# V2_eagle7.net
KiCad netlist of a schematic drawn in EAGLE
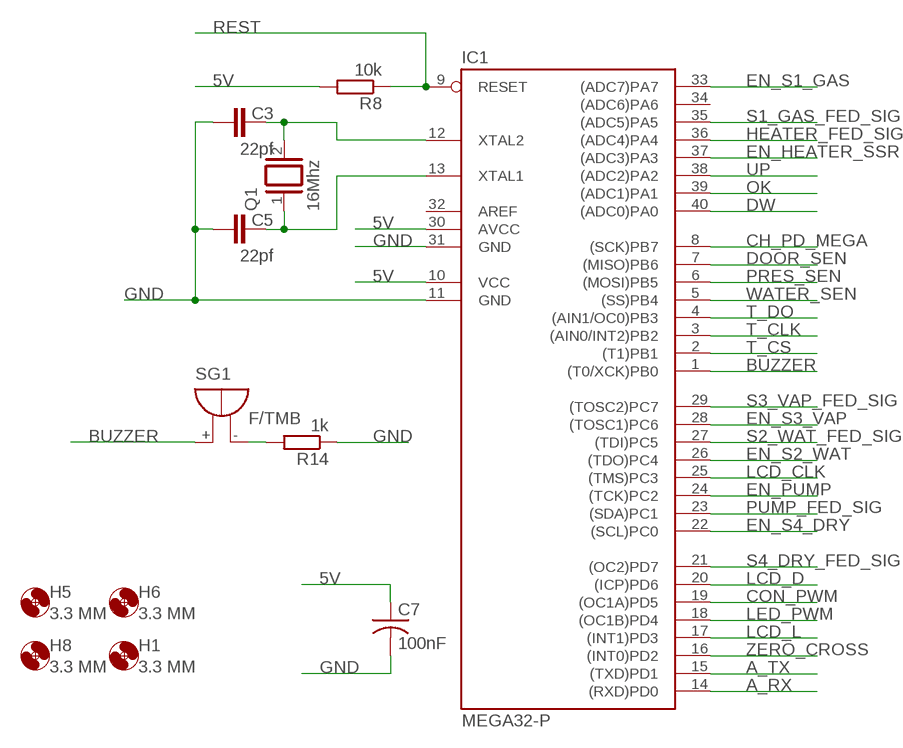
[diagram p0: schematic, sheet 1]
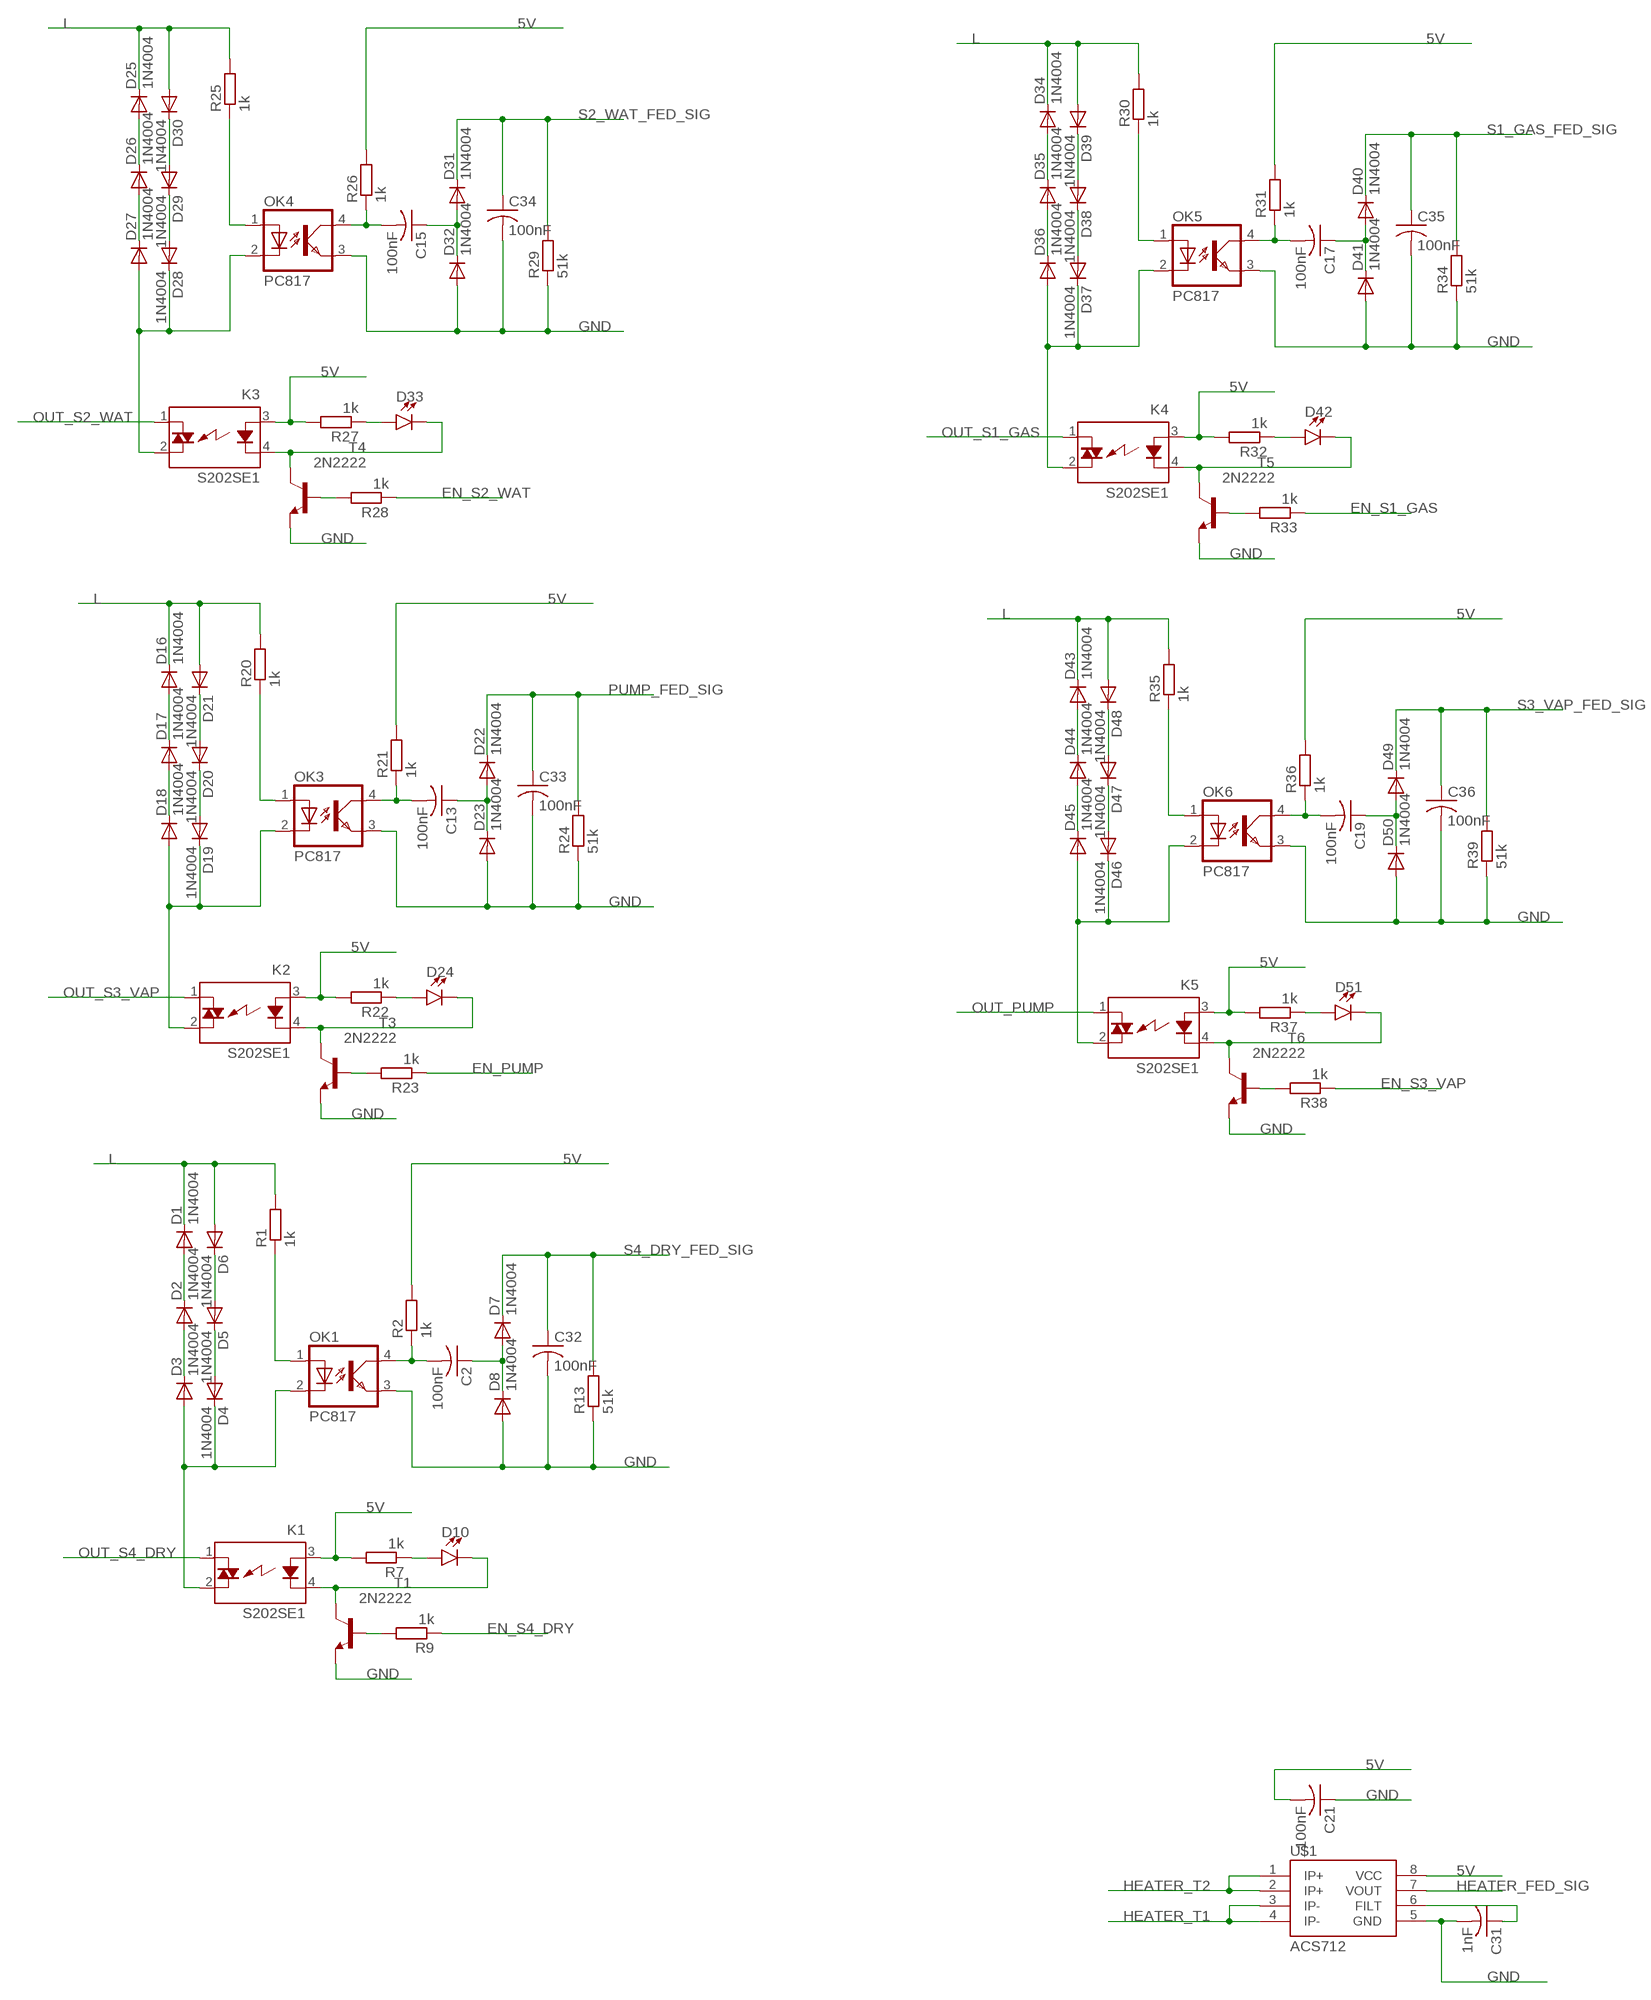
[diagram p1: schematic, sheet 2]
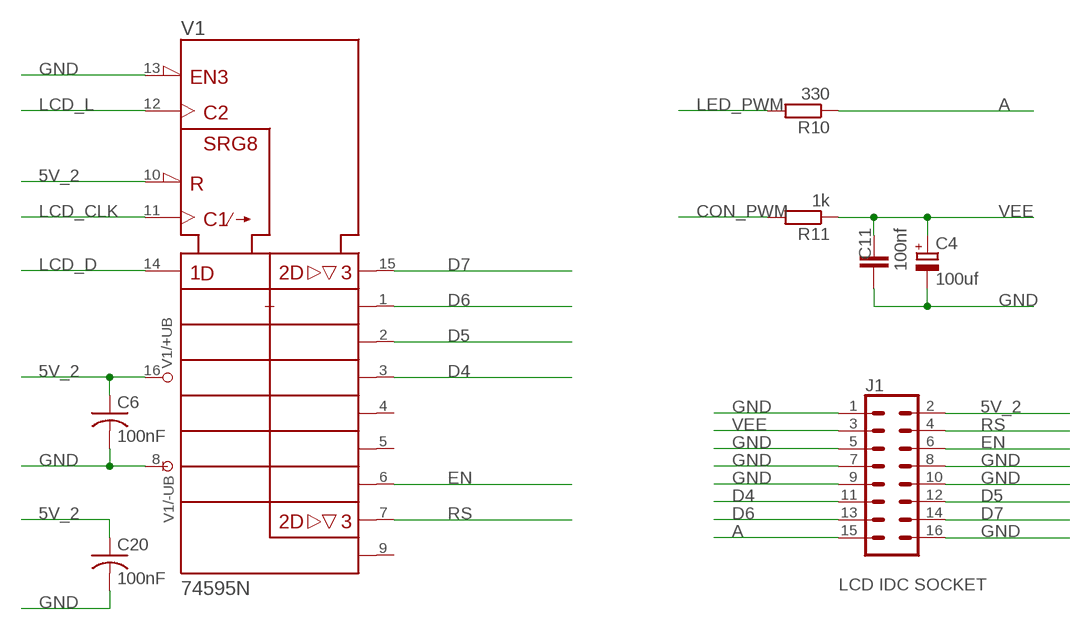
[diagram p2: schematic, sheet 3]
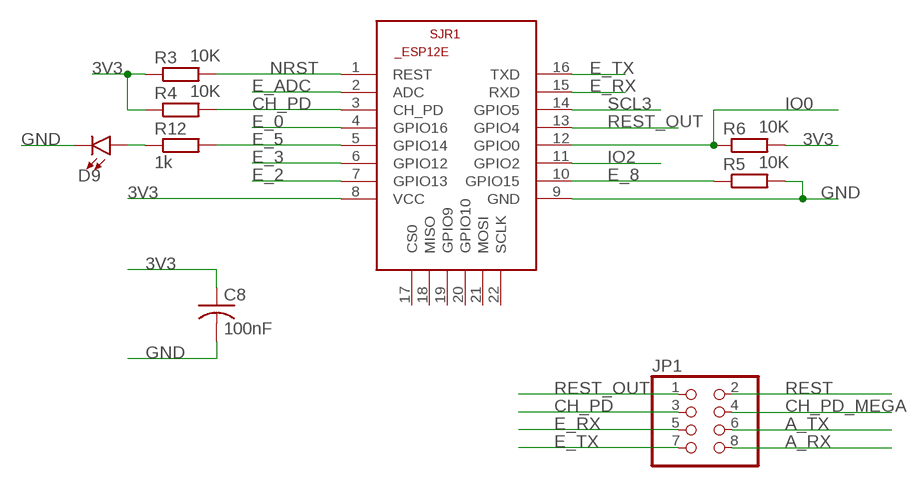
[diagram p3: schematic, sheet 4]
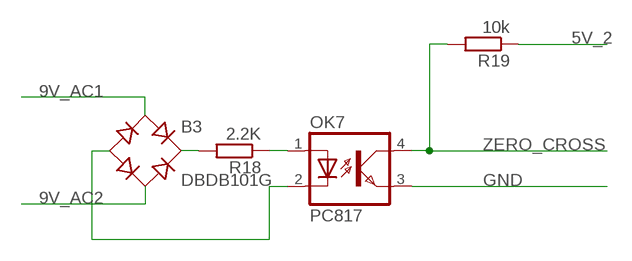
[diagram p4: schematic, sheet 5]
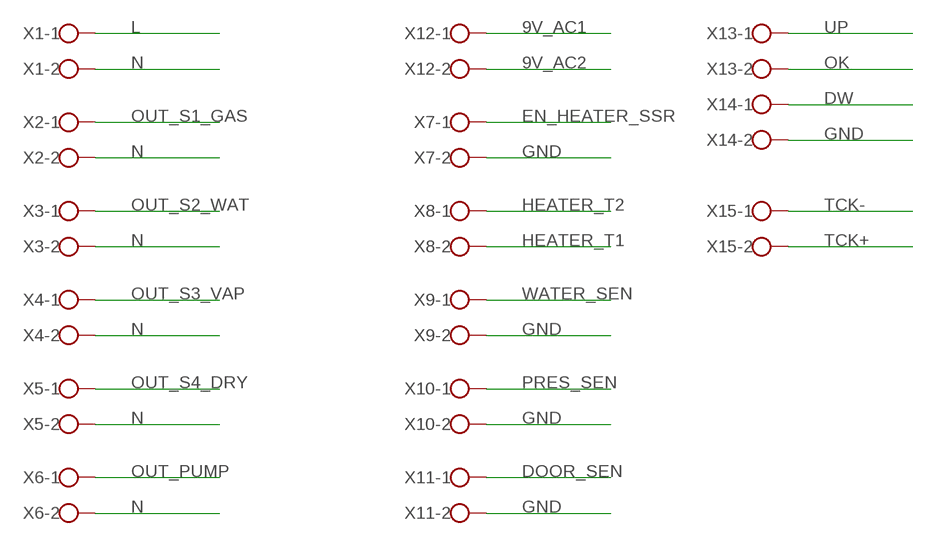
[diagram p5: schematic, sheet 6]
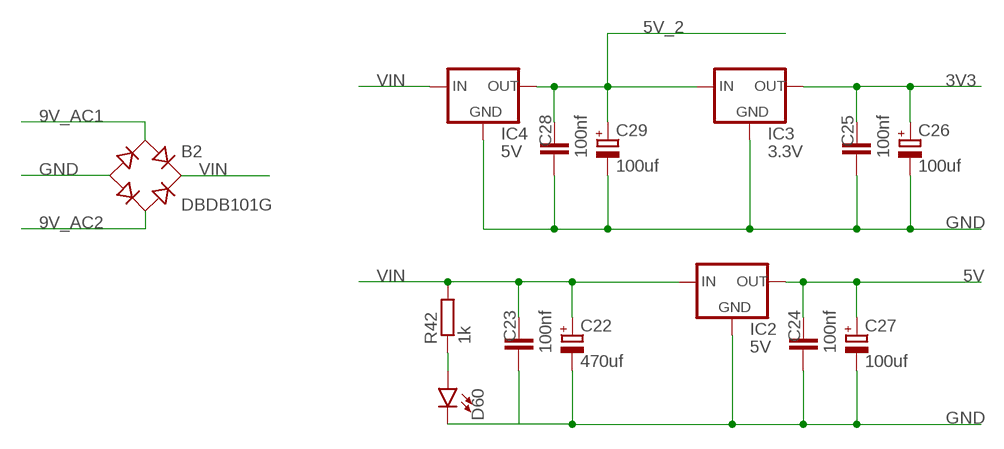
[diagram p6: schematic, sheet 7]
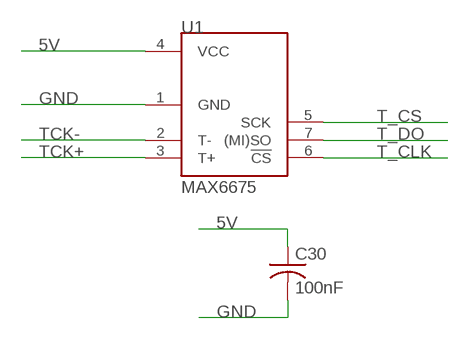
[diagram p7: schematic, sheet 8]

(export (version "E")
  (design (tool "Eeschema 10.0.6"))
  (components
    (comp (ref "C30")
      (value "100nF")
      (footprint "eagle-import:C050-035X075")
      (libsource (lib "eagle-import") (part "C-US050-035X075"))
    )
    (comp (ref "U1")
      (value "MAX6675")
      (footprint "eagle-import:SOIC8")
      (libsource (lib "eagle-import") (part "MAX6675"))
    )
    (comp (ref "C2")
      (value "100nF")
      (footprint "eagle-import:C050-035X075")
      (libsource (lib "eagle-import") (part "C-US050-035X075"))
    )
    (comp (ref "C13")
      (value "100nF")
      (footprint "eagle-import:C050-035X075")
      (libsource (lib "eagle-import") (part "C-US050-035X075"))
    )
    (comp (ref "C15")
      (value "100nF")
      (footprint "eagle-import:C050-035X075")
      (libsource (lib "eagle-import") (part "C-US050-035X075"))
    )
    (comp (ref "C17")
      (value "100nF")
      (footprint "eagle-import:C050-035X075")
      (libsource (lib "eagle-import") (part "C-US050-035X075"))
    )
    (comp (ref "C19")
      (value "100nF")
      (footprint "eagle-import:C050-035X075")
      (libsource (lib "eagle-import") (part "C-US050-035X075"))
    )
    (comp (ref "C21")
      (value "100nF")
      (footprint "eagle-import:C050-035X075")
      (libsource (lib "eagle-import") (part "C-US050-035X075"))
    )
    (comp (ref "C31")
      (value "1nF")
      (footprint "eagle-import:C050-035X075")
      (libsource (lib "eagle-import") (part "C-US050-035X075"))
    )
    (comp (ref "C32")
      (value "100nF")
      (footprint "eagle-import:C050-035X075")
      (libsource (lib "eagle-import") (part "C-US050-035X075"))
    )
    (comp (ref "C33")
      (value "100nF")
      (footprint "eagle-import:C050-035X075")
      (libsource (lib "eagle-import") (part "C-US050-035X075"))
    )
    (comp (ref "C34")
      (value "100nF")
      (footprint "eagle-import:C050-035X075")
      (libsource (lib "eagle-import") (part "C-US050-035X075"))
    )
    (comp (ref "C35")
      (value "100nF")
      (footprint "eagle-import:C050-035X075")
      (libsource (lib "eagle-import") (part "C-US050-035X075"))
    )
    (comp (ref "C36")
      (value "100nF")
      (footprint "eagle-import:C050-035X075")
      (libsource (lib "eagle-import") (part "C-US050-035X075"))
    )
    (comp (ref "D1")
      (value "1N4004")
      (footprint "eagle-import:DO41-10")
      (libsource (lib "eagle-import") (part "1N4004"))
    )
    (comp (ref "D2")
      (value "1N4004")
      (footprint "eagle-import:DO41-10")
      (libsource (lib "eagle-import") (part "1N4004"))
    )
    (comp (ref "D3")
      (value "1N4004")
      (footprint "eagle-import:DO41-10")
      (libsource (lib "eagle-import") (part "1N4004"))
    )
    (comp (ref "D4")
      (value "1N4004")
      (footprint "eagle-import:DO41-10")
      (libsource (lib "eagle-import") (part "1N4004"))
    )
    (comp (ref "D5")
      (value "1N4004")
      (footprint "eagle-import:DO41-10")
      (libsource (lib "eagle-import") (part "1N4004"))
    )
    (comp (ref "D6")
      (value "1N4004")
      (footprint "eagle-import:DO41-10")
      (libsource (lib "eagle-import") (part "1N4004"))
    )
    (comp (ref "D7")
      (value "1N4004")
      (footprint "eagle-import:DO41-10")
      (libsource (lib "eagle-import") (part "1N4004"))
    )
    (comp (ref "D8")
      (value "1N4004")
      (footprint "eagle-import:DO41-10")
      (libsource (lib "eagle-import") (part "1N4004"))
    )
    (comp (ref "D10")
      (value "LED5MM")
      (footprint "eagle-import:LED_5MM")
      (libsource (lib "eagle-import") (part "LED5MM"))
    )
    (comp (ref "D16")
      (value "1N4004")
      (footprint "eagle-import:DO41-10")
      (libsource (lib "eagle-import") (part "1N4004"))
    )
    (comp (ref "D17")
      (value "1N4004")
      (footprint "eagle-import:DO41-10")
      (libsource (lib "eagle-import") (part "1N4004"))
    )
    (comp (ref "D18")
      (value "1N4004")
      (footprint "eagle-import:DO41-10")
      (libsource (lib "eagle-import") (part "1N4004"))
    )
    (comp (ref "D19")
      (value "1N4004")
      (footprint "eagle-import:DO41-10")
      (libsource (lib "eagle-import") (part "1N4004"))
    )
    (comp (ref "D20")
      (value "1N4004")
      (footprint "eagle-import:DO41-10")
      (libsource (lib "eagle-import") (part "1N4004"))
    )
    (comp (ref "D21")
      (value "1N4004")
      (footprint "eagle-import:DO41-10")
      (libsource (lib "eagle-import") (part "1N4004"))
    )
    (comp (ref "D22")
      (value "1N4004")
      (footprint "eagle-import:DO41-10")
      (libsource (lib "eagle-import") (part "1N4004"))
    )
    (comp (ref "D23")
      (value "1N4004")
      (footprint "eagle-import:DO41-10")
      (libsource (lib "eagle-import") (part "1N4004"))
    )
    (comp (ref "D24")
      (value "LED5MM")
      (footprint "eagle-import:LED_5MM")
      (libsource (lib "eagle-import") (part "LED5MM"))
    )
    (comp (ref "D25")
      (value "1N4004")
      (footprint "eagle-import:DO41-10")
      (libsource (lib "eagle-import") (part "1N4004"))
    )
    (comp (ref "D26")
      (value "1N4004")
      (footprint "eagle-import:DO41-10")
      (libsource (lib "eagle-import") (part "1N4004"))
    )
    (comp (ref "D27")
      (value "1N4004")
      (footprint "eagle-import:DO41-10")
      (libsource (lib "eagle-import") (part "1N4004"))
    )
    (comp (ref "D28")
      (value "1N4004")
      (footprint "eagle-import:DO41-10")
      (libsource (lib "eagle-import") (part "1N4004"))
    )
    (comp (ref "D29")
      (value "1N4004")
      (footprint "eagle-import:DO41-10")
      (libsource (lib "eagle-import") (part "1N4004"))
    )
    (comp (ref "D30")
      (value "1N4004")
      (footprint "eagle-import:DO41-10")
      (libsource (lib "eagle-import") (part "1N4004"))
    )
    (comp (ref "D31")
      (value "1N4004")
      (footprint "eagle-import:DO41-10")
      (libsource (lib "eagle-import") (part "1N4004"))
    )
    (comp (ref "D32")
      (value "1N4004")
      (footprint "eagle-import:DO41-10")
      (libsource (lib "eagle-import") (part "1N4004"))
    )
    (comp (ref "D33")
      (value "LED5MM")
      (footprint "eagle-import:LED_5MM")
      (libsource (lib "eagle-import") (part "LED5MM"))
    )
    (comp (ref "D34")
      (value "1N4004")
      (footprint "eagle-import:DO41-10")
      (libsource (lib "eagle-import") (part "1N4004"))
    )
    (comp (ref "D35")
      (value "1N4004")
      (footprint "eagle-import:DO41-10")
      (libsource (lib "eagle-import") (part "1N4004"))
    )
    (comp (ref "D36")
      (value "1N4004")
      (footprint "eagle-import:DO41-10")
      (libsource (lib "eagle-import") (part "1N4004"))
    )
    (comp (ref "D37")
      (value "1N4004")
      (footprint "eagle-import:DO41-10")
      (libsource (lib "eagle-import") (part "1N4004"))
    )
    (comp (ref "D38")
      (value "1N4004")
      (footprint "eagle-import:DO41-10")
      (libsource (lib "eagle-import") (part "1N4004"))
    )
    (comp (ref "D39")
      (value "1N4004")
      (footprint "eagle-import:DO41-10")
      (libsource (lib "eagle-import") (part "1N4004"))
    )
    (comp (ref "D40")
      (value "1N4004")
      (footprint "eagle-import:DO41-10")
      (libsource (lib "eagle-import") (part "1N4004"))
    )
    (comp (ref "D41")
      (value "1N4004")
      (footprint "eagle-import:DO41-10")
      (libsource (lib "eagle-import") (part "1N4004"))
    )
    (comp (ref "D42")
      (value "LED5MM")
      (footprint "eagle-import:LED_5MM")
      (libsource (lib "eagle-import") (part "LED5MM"))
    )
    (comp (ref "D43")
      (value "1N4004")
      (footprint "eagle-import:DO41-10")
      (libsource (lib "eagle-import") (part "1N4004"))
    )
    (comp (ref "D44")
      (value "1N4004")
      (footprint "eagle-import:DO41-10")
      (libsource (lib "eagle-import") (part "1N4004"))
    )
    (comp (ref "D45")
      (value "1N4004")
      (footprint "eagle-import:DO41-10")
      (libsource (lib "eagle-import") (part "1N4004"))
    )
    (comp (ref "D46")
      (value "1N4004")
      (footprint "eagle-import:DO41-10")
      (libsource (lib "eagle-import") (part "1N4004"))
    )
    (comp (ref "D47")
      (value "1N4004")
      (footprint "eagle-import:DO41-10")
      (libsource (lib "eagle-import") (part "1N4004"))
    )
    (comp (ref "D48")
      (value "1N4004")
      (footprint "eagle-import:DO41-10")
      (libsource (lib "eagle-import") (part "1N4004"))
    )
    (comp (ref "D49")
      (value "1N4004")
      (footprint "eagle-import:DO41-10")
      (libsource (lib "eagle-import") (part "1N4004"))
    )
    (comp (ref "D50")
      (value "1N4004")
      (footprint "eagle-import:DO41-10")
      (libsource (lib "eagle-import") (part "1N4004"))
    )
    (comp (ref "D51")
      (value "LED5MM")
      (footprint "eagle-import:LED_5MM")
      (libsource (lib "eagle-import") (part "LED5MM"))
    )
    (comp (ref "K1")
      (value "S202SE1")
      (footprint "eagle-import:S2XXEX")
      (libsource (lib "eagle-import") (part "S202SE1"))
    )
    (comp (ref "K2")
      (value "S202SE1")
      (footprint "eagle-import:S2XXEX")
      (libsource (lib "eagle-import") (part "S202SE1"))
    )
    (comp (ref "K3")
      (value "S202SE1")
      (footprint "eagle-import:S2XXEX")
      (libsource (lib "eagle-import") (part "S202SE1"))
    )
    (comp (ref "K4")
      (value "S202SE1")
      (footprint "eagle-import:S2XXEX")
      (libsource (lib "eagle-import") (part "S202SE1"))
    )
    (comp (ref "K5")
      (value "S202SE1")
      (footprint "eagle-import:S2XXEX")
      (libsource (lib "eagle-import") (part "S202SE1"))
    )
    (comp (ref "OK1")
      (value "PC817")
      (footprint "eagle-import:DIL04")
      (libsource (lib "eagle-import") (part "PC817"))
    )
    (comp (ref "OK3")
      (value "PC817")
      (footprint "eagle-import:DIL04")
      (libsource (lib "eagle-import") (part "PC817"))
    )
    (comp (ref "OK4")
      (value "PC817")
      (footprint "eagle-import:DIL04")
      (libsource (lib "eagle-import") (part "PC817"))
    )
    (comp (ref "OK5")
      (value "PC817")
      (footprint "eagle-import:DIL04")
      (libsource (lib "eagle-import") (part "PC817"))
    )
    (comp (ref "OK6")
      (value "PC817")
      (footprint "eagle-import:DIL04")
      (libsource (lib "eagle-import") (part "PC817"))
    )
    (comp (ref "R1")
      (value "1k")
      (footprint "eagle-import:0207_10")
      (libsource (lib "eagle-import") (part "R-EU_0207/10"))
    )
    (comp (ref "R2")
      (value "1k")
      (footprint "eagle-import:0207_10")
      (libsource (lib "eagle-import") (part "R-EU_0207/10"))
    )
    (comp (ref "R7")
      (value "1k")
      (footprint "eagle-import:0207_10")
      (libsource (lib "eagle-import") (part "R-EU_0207/10"))
    )
    (comp (ref "R9")
      (value "1k")
      (footprint "eagle-import:0207_10")
      (libsource (lib "eagle-import") (part "R-EU_0207/10"))
    )
    (comp (ref "R13")
      (value "51k")
      (footprint "eagle-import:0207_10")
      (libsource (lib "eagle-import") (part "R-EU_0207/10"))
    )
    (comp (ref "R20")
      (value "1k")
      (footprint "eagle-import:0207_10")
      (libsource (lib "eagle-import") (part "R-EU_0207/10"))
    )
    (comp (ref "R21")
      (value "1k")
      (footprint "eagle-import:0207_10")
      (libsource (lib "eagle-import") (part "R-EU_0207/10"))
    )
    (comp (ref "R22")
      (value "1k")
      (footprint "eagle-import:0207_10")
      (libsource (lib "eagle-import") (part "R-EU_0207/10"))
    )
    (comp (ref "R23")
      (value "1k")
      (footprint "eagle-import:0207_10")
      (libsource (lib "eagle-import") (part "R-EU_0207/10"))
    )
    (comp (ref "R24")
      (value "51k")
      (footprint "eagle-import:0207_10")
      (libsource (lib "eagle-import") (part "R-EU_0207/10"))
    )
    (comp (ref "R25")
      (value "1k")
      (footprint "eagle-import:0207_10")
      (libsource (lib "eagle-import") (part "R-EU_0207/10"))
    )
    (comp (ref "R26")
      (value "1k")
      (footprint "eagle-import:0207_10")
      (libsource (lib "eagle-import") (part "R-EU_0207/10"))
    )
    (comp (ref "R27")
      (value "1k")
      (footprint "eagle-import:0207_10")
      (libsource (lib "eagle-import") (part "R-EU_0207/10"))
    )
    (comp (ref "R28")
      (value "1k")
      (footprint "eagle-import:0207_10")
      (libsource (lib "eagle-import") (part "R-EU_0207/10"))
    )
    (comp (ref "R29")
      (value "51k")
      (footprint "eagle-import:0207_10")
      (libsource (lib "eagle-import") (part "R-EU_0207/10"))
    )
    (comp (ref "R30")
      (value "1k")
      (footprint "eagle-import:0207_10")
      (libsource (lib "eagle-import") (part "R-EU_0207/10"))
    )
    (comp (ref "R31")
      (value "1k")
      (footprint "eagle-import:0207_10")
      (libsource (lib "eagle-import") (part "R-EU_0207/10"))
    )
    (comp (ref "R32")
      (value "1k")
      (footprint "eagle-import:0207_10")
      (libsource (lib "eagle-import") (part "R-EU_0207/10"))
    )
    (comp (ref "R33")
      (value "1k")
      (footprint "eagle-import:0207_10")
      (libsource (lib "eagle-import") (part "R-EU_0207/10"))
    )
    (comp (ref "R34")
      (value "51k")
      (footprint "eagle-import:0207_10")
      (libsource (lib "eagle-import") (part "R-EU_0207/10"))
    )
    (comp (ref "R35")
      (value "1k")
      (footprint "eagle-import:0207_10")
      (libsource (lib "eagle-import") (part "R-EU_0207/10"))
    )
    (comp (ref "R36")
      (value "1k")
      (footprint "eagle-import:0207_10")
      (libsource (lib "eagle-import") (part "R-EU_0207/10"))
    )
    (comp (ref "R37")
      (value "1k")
      (footprint "eagle-import:0207_10")
      (libsource (lib "eagle-import") (part "R-EU_0207/10"))
    )
    (comp (ref "R38")
      (value "1k")
      (footprint "eagle-import:0207_10")
      (libsource (lib "eagle-import") (part "R-EU_0207/10"))
    )
    (comp (ref "R39")
      (value "51k")
      (footprint "eagle-import:0207_10")
      (libsource (lib "eagle-import") (part "R-EU_0207/10"))
    )
    (comp (ref "T1")
      (value "2N2222")
      (footprint "eagle-import:TO92-EBC-OVAL")
      (libsource (lib "eagle-import") (part "2N2222"))
    )
    (comp (ref "T3")
      (value "2N2222")
      (footprint "eagle-import:TO92-EBC-OVAL")
      (libsource (lib "eagle-import") (part "2N2222"))
    )
    (comp (ref "T4")
      (value "2N2222")
      (footprint "eagle-import:TO92-EBC-OVAL")
      (libsource (lib "eagle-import") (part "2N2222"))
    )
    (comp (ref "T5")
      (value "2N2222")
      (footprint "eagle-import:TO92-EBC-OVAL")
      (libsource (lib "eagle-import") (part "2N2222"))
    )
    (comp (ref "T6")
      (value "2N2222")
      (footprint "eagle-import:TO92-EBC-OVAL")
      (libsource (lib "eagle-import") (part "2N2222"))
    )
    (comp (ref "U$1")
      (value "ACS712")
      (footprint "eagle-import:SO08")
      (libsource (lib "eagle-import") (part "ACS712"))
    )
    (comp (ref "B2")
      (value "DBDB101G")
      (footprint "eagle-import:DB")
      (libsource (lib "eagle-import") (part "DB?GDB101"))
    )
    (comp (ref "C22")
      (value "470uf")
      (footprint "eagle-import:E3,5-8")
      (libsource (lib "eagle-import") (part "CPOL-EUE3.5-8"))
    )
    (comp (ref "C23")
      (value "100nf")
      (footprint "eagle-import:C050-030X075")
      (libsource (lib "eagle-import") (part "C-EU050-030X075"))
    )
    (comp (ref "C24")
      (value "100nf")
      (footprint "eagle-import:C050-030X075")
      (libsource (lib "eagle-import") (part "C-EU050-030X075"))
    )
    (comp (ref "C25")
      (value "100nf")
      (footprint "eagle-import:C050-030X075")
      (libsource (lib "eagle-import") (part "C-EU050-030X075"))
    )
    (comp (ref "C26")
      (value "100uf")
      (footprint "eagle-import:E3,5-8")
      (libsource (lib "eagle-import") (part "CPOL-EUE3.5-8"))
    )
    (comp (ref "C27")
      (value "100uf")
      (footprint "eagle-import:E3,5-8")
      (libsource (lib "eagle-import") (part "CPOL-EUE3.5-8"))
    )
    (comp (ref "C28")
      (value "100nf")
      (footprint "eagle-import:C050-030X075")
      (libsource (lib "eagle-import") (part "C-EU050-030X075"))
    )
    (comp (ref "C29")
      (value "100uf")
      (footprint "eagle-import:E3,5-8")
      (libsource (lib "eagle-import") (part "CPOL-EUE3.5-8"))
    )
    (comp (ref "D60")
      (value "LED5MM")
      (footprint "eagle-import:LED_5MM")
      (libsource (lib "eagle-import") (part "LED5MM"))
    )
    (comp (ref "IC2")
      (value "5V")
      (footprint "eagle-import:78XXL")
      (libsource (lib "eagle-import") (part "V_REG_78XXSIDE"))
    )
    (comp (ref "IC3")
      (value "3.3V")
      (footprint "eagle-import:78XXL")
      (libsource (lib "eagle-import") (part "V_REG_78XXSIDE"))
    )
    (comp (ref "IC4")
      (value "5V")
      (footprint "eagle-import:78XXL")
      (libsource (lib "eagle-import") (part "V_REG_78XXSIDE"))
    )
    (comp (ref "R42")
      (value "1k")
      (footprint "eagle-import:0207_10")
      (libsource (lib "eagle-import") (part "R-EU_0207/10"))
    )
    (comp (ref "X1")
      (value "W237-102")
      (footprint "eagle-import:W237-102")
      (fields (field (name "MPN") "237-102"))
      (libsource (lib "eagle-import") (part "W237-102"))
    )
    (comp (ref "X2")
      (value "W237-102")
      (footprint "eagle-import:W237-102")
      (fields (field (name "MPN") "237-102"))
      (libsource (lib "eagle-import") (part "W237-102"))
    )
    (comp (ref "X3")
      (value "W237-102")
      (footprint "eagle-import:W237-102")
      (fields (field (name "MPN") "237-102"))
      (libsource (lib "eagle-import") (part "W237-102"))
    )
    (comp (ref "X4")
      (value "W237-102")
      (footprint "eagle-import:W237-102")
      (fields (field (name "MPN") "237-102"))
      (libsource (lib "eagle-import") (part "W237-102"))
    )
    (comp (ref "X5")
      (value "W237-102")
      (footprint "eagle-import:W237-102")
      (fields (field (name "MPN") "237-102"))
      (libsource (lib "eagle-import") (part "W237-102"))
    )
    (comp (ref "X6")
      (value "W237-102")
      (footprint "eagle-import:W237-102")
      (fields (field (name "MPN") "237-102"))
      (libsource (lib "eagle-import") (part "W237-102"))
    )
    (comp (ref "X7")
      (value "W237-102")
      (footprint "eagle-import:W237-102")
      (fields (field (name "MPN") "237-102"))
      (libsource (lib "eagle-import") (part "W237-102"))
    )
    (comp (ref "X8")
      (value "W237-102")
      (footprint "eagle-import:W237-102")
      (fields (field (name "MPN") "237-102"))
      (libsource (lib "eagle-import") (part "W237-102"))
    )
    (comp (ref "X9")
      (value "W237-102")
      (footprint "eagle-import:W237-102")
      (fields (field (name "MPN") "237-102"))
      (libsource (lib "eagle-import") (part "W237-102"))
    )
    (comp (ref "X10")
      (value "W237-102")
      (footprint "eagle-import:W237-102")
      (fields (field (name "MPN") "237-102"))
      (libsource (lib "eagle-import") (part "W237-102"))
    )
    (comp (ref "X11")
      (value "W237-102")
      (footprint "eagle-import:W237-102")
      (fields (field (name "MPN") "237-102"))
      (libsource (lib "eagle-import") (part "W237-102"))
    )
    (comp (ref "X12")
      (value "W237-102")
      (footprint "eagle-import:W237-102")
      (fields (field (name "MPN") "237-102"))
      (libsource (lib "eagle-import") (part "W237-102"))
    )
    (comp (ref "X13")
      (value "W237-102")
      (footprint "eagle-import:W237-102")
      (fields (field (name "MPN") "237-102"))
      (libsource (lib "eagle-import") (part "W237-102"))
    )
    (comp (ref "X14")
      (value "W237-102")
      (footprint "eagle-import:W237-102")
      (fields (field (name "MPN") "237-102"))
      (libsource (lib "eagle-import") (part "W237-102"))
    )
    (comp (ref "X15")
      (value "W237-102")
      (footprint "eagle-import:W237-102")
      (fields (field (name "MPN") "237-102"))
      (libsource (lib "eagle-import") (part "W237-102"))
    )
    (comp (ref "B3")
      (value "DBDB101G")
      (footprint "eagle-import:DB")
      (libsource (lib "eagle-import") (part "DB?GDB101"))
    )
    (comp (ref "OK7")
      (value "PC817")
      (footprint "eagle-import:DIL04")
      (libsource (lib "eagle-import") (part "PC817"))
    )
    (comp (ref "R18")
      (value "2.2K")
      (footprint "eagle-import:0207_10")
      (libsource (lib "eagle-import") (part "R-EU_0207/10"))
    )
    (comp (ref "R19")
      (value "10k")
      (footprint "eagle-import:0207_10")
      (libsource (lib "eagle-import") (part "R-EU_0207/10"))
    )
    (comp (ref "C8")
      (value "100nF")
      (footprint "eagle-import:C050-035X075")
      (libsource (lib "eagle-import") (part "C-US050-035X075"))
    )
    (comp (ref "D9")
      (value "LED5MM")
      (footprint "eagle-import:LED_5MM")
      (libsource (lib "eagle-import") (part "LED5MM"))
    )
    (comp (ref "JP1")
      (value "PINHD-2X4")
      (footprint "eagle-import:2X04")
      (libsource (lib "eagle-import") (part "PINHD-2X4"))
    )
    (comp (ref "R3")
      (value "10K")
      (footprint "eagle-import:0207_10")
      (libsource (lib "eagle-import") (part "rcl@1_R-EU_0207/10"))
    )
    (comp (ref "R4")
      (value "10K")
      (footprint "eagle-import:0207_10")
      (libsource (lib "eagle-import") (part "rcl@1_R-EU_0207/10"))
    )
    (comp (ref "R5")
      (value "10K")
      (footprint "eagle-import:0207_10")
      (libsource (lib "eagle-import") (part "rcl@1_R-EU_0207/10"))
    )
    (comp (ref "R6")
      (value "10K")
      (footprint "eagle-import:0207_10")
      (libsource (lib "eagle-import") (part "rcl@1_R-EU_0207/10"))
    )
    (comp (ref "R12")
      (value "1k")
      (footprint "eagle-import:0207_10")
      (libsource (lib "eagle-import") (part "R-EU_0207/10"))
    )
    (comp (ref "SJR1")
      (value "ESP8266-12EESP12E")
      (footprint "eagle-import:ESP8266-ESP12E")
      (libsource (lib "eagle-import") (part "ESP8266-12EESP12E"))
    )
    (comp (ref "C4")
      (value "100uf")
      (footprint "eagle-import:E3,5-8")
      (libsource (lib "eagle-import") (part "CPOL-EUE3.5-8"))
    )
    (comp (ref "C6")
      (value "100nF")
      (footprint "eagle-import:C050-035X075")
      (libsource (lib "eagle-import") (part "C-US050-035X075"))
    )
    (comp (ref "C11")
      (value "100nf")
      (footprint "eagle-import:C050-030X075")
      (libsource (lib "eagle-import") (part "C-EU050-030X075"))
    )
    (comp (ref "C20")
      (value "100nF")
      (footprint "eagle-import:C050-035X075")
      (libsource (lib "eagle-import") (part "C-US050-035X075"))
    )
    (comp (ref "J1")
      (value "CONN_08X2")
      (footprint "eagle-import:2X8")
      (libsource (lib "eagle-import") (part "CONN_08X2"))
    )
    (comp (ref "R10")
      (value "330")
      (footprint "eagle-import:0207_10")
      (libsource (lib "eagle-import") (part "R-EU_0207/10"))
    )
    (comp (ref "R11")
      (value "1k")
      (footprint "eagle-import:0207_10")
      (libsource (lib "eagle-import") (part "R-EU_0207/10"))
    )
    (comp (ref "V1")
      (value "74595N")
      (footprint "eagle-import:DIL16")
      (libsource (lib "eagle-import") (part "74595N"))
    )
    (comp (ref "C3")
      (value "22pf")
      (footprint "eagle-import:C050-030X075")
      (libsource (lib "eagle-import") (part "C-EU050-030X075"))
    )
    (comp (ref "C5")
      (value "22pf")
      (footprint "eagle-import:C050-030X075")
      (libsource (lib "eagle-import") (part "C-EU050-030X075"))
    )
    (comp (ref "C7")
      (value "100nF")
      (footprint "eagle-import:C050-035X075")
      (libsource (lib "eagle-import") (part "C-US050-035X075"))
    )
    (comp (ref "H1")
      (value "3.3 MM")
      (footprint "eagle-import:3,3")
      (libsource (lib "eagle-import") (part "MOUNT-HOLE3.3"))
    )
    (comp (ref "H5")
      (value "3.3 MM")
      (footprint "eagle-import:3,3")
      (libsource (lib "eagle-import") (part "MOUNT-HOLE3.3"))
    )
    (comp (ref "H6")
      (value "3.3 MM")
      (footprint "eagle-import:3,3")
      (libsource (lib "eagle-import") (part "MOUNT-HOLE3.3"))
    )
    (comp (ref "H8")
      (value "3.3 MM")
      (footprint "eagle-import:3,3")
      (libsource (lib "eagle-import") (part "MOUNT-HOLE3.3"))
    )
    (comp (ref "IC1")
      (value "MEGA32-P")
      (footprint "eagle-import:DIL40")
      (fields (field (name "MPN") "ATMEGA32-16PU"))
      (libsource (lib "eagle-import") (part "MEGA32-P"))
    )
    (comp (ref "Q1")
      (value "16Mhz")
      (footprint "eagle-import:QS")
      (libsource (lib "eagle-import") (part "XTAL/S"))
    )
    (comp (ref "R8")
      (value "10k")
      (footprint "eagle-import:0207_10")
      (libsource (lib "eagle-import") (part "R-EU_0207/10"))
    )
    (comp (ref "R14")
      (value "1k")
      (footprint "eagle-import:0207_10")
      (libsource (lib "eagle-import") (part "R-EU_0207/10"))
    )
    (comp (ref "SG1")
      (value "F/TMB")
      (footprint "eagle-import:F_TMB")
      (libsource (lib "eagle-import") (part "F/TMB"))
    )
  )
  (nets
    (net (code "1") (name "3V3") (class "Default")
      (node (ref "C25") (pin "2") (pinfunction "2_2") (pintype "passive"))
      (node (ref "C26") (pin "+") (pinfunction "+_+") (pintype "passive"))
      (node (ref "C8") (pin "1") (pinfunction "1_1") (pintype "passive"))
      (node (ref "IC3") (pin "OUT") (pinfunction "OUT_OUT") (pintype "output"))
      (node (ref "R3") (pin "1") (pinfunction "1_1") (pintype "passive"))
      (node (ref "R4") (pin "1") (pinfunction "1_1") (pintype "passive"))
      (node (ref "R6") (pin "2") (pinfunction "2_2") (pintype "passive"))
      (node (ref "SJR1") (pin "8") (pinfunction "VCC_8") (pintype "bidirectional"))
    )
    (net (code "2") (name "5V") (class "Default")
      (node (ref "C21") (pin "2") (pinfunction "2_2") (pintype "passive"))
      (node (ref "C24") (pin "2") (pinfunction "2_2") (pintype "passive"))
      (node (ref "C27") (pin "+") (pinfunction "+_+") (pintype "passive"))
      (node (ref "C30") (pin "1") (pinfunction "1_1") (pintype "passive"))
      (node (ref "C7") (pin "1") (pinfunction "1_1") (pintype "passive"))
      (node (ref "IC1") (pin "10") (pinfunction "VCC_10") (pintype "power_in"))
      (node (ref "IC1") (pin "30") (pinfunction "AVCC_30") (pintype "power_in"))
      (node (ref "IC2") (pin "OUT") (pinfunction "OUT_OUT") (pintype "output"))
      (node (ref "K1") (pin "3") (pinfunction "A_3") (pintype "passive"))
      (node (ref "K2") (pin "3") (pinfunction "A_3") (pintype "passive"))
      (node (ref "K3") (pin "3") (pinfunction "A_3") (pintype "passive"))
      (node (ref "K4") (pin "3") (pinfunction "A_3") (pintype "passive"))
      (node (ref "K5") (pin "3") (pinfunction "A_3") (pintype "passive"))
      (node (ref "R2") (pin "2") (pinfunction "2_2") (pintype "passive"))
      (node (ref "R21") (pin "2") (pinfunction "2_2") (pintype "passive"))
      (node (ref "R22") (pin "2") (pinfunction "2_2") (pintype "passive"))
      (node (ref "R26") (pin "2") (pinfunction "2_2") (pintype "passive"))
      (node (ref "R27") (pin "2") (pinfunction "2_2") (pintype "passive"))
      (node (ref "R31") (pin "2") (pinfunction "2_2") (pintype "passive"))
      (node (ref "R32") (pin "2") (pinfunction "2_2") (pintype "passive"))
      (node (ref "R36") (pin "2") (pinfunction "2_2") (pintype "passive"))
      (node (ref "R37") (pin "2") (pinfunction "2_2") (pintype "passive"))
      (node (ref "R7") (pin "2") (pinfunction "2_2") (pintype "passive"))
      (node (ref "R8") (pin "2") (pinfunction "2_2") (pintype "passive"))
      (node (ref "U$1") (pin "8") (pinfunction "VCC_8") (pintype "bidirectional"))
      (node (ref "U1") (pin "4") (pinfunction "VCC_4") (pintype "bidirectional"))
    )
    (net (code "3") (name "5V_2") (class "Default")
      (node (ref "C20") (pin "1") (pinfunction "1_1") (pintype "passive"))
      (node (ref "C28") (pin "2") (pinfunction "2_2") (pintype "passive"))
      (node (ref "C29") (pin "+") (pinfunction "+_+") (pintype "passive"))
      (node (ref "C6") (pin "1") (pinfunction "1_1") (pintype "passive"))
      (node (ref "IC3") (pin "IN") (pinfunction "IN_IN") (pintype "input"))
      (node (ref "IC4") (pin "OUT") (pinfunction "OUT_OUT") (pintype "output"))
      (node (ref "J1") (pin "2") (pinfunction "2_2") (pintype "passive"))
      (node (ref "R19") (pin "1") (pinfunction "1_1") (pintype "passive"))
      (node (ref "V1") (pin "10") (pinfunction "~{SRCLR}_10") (pintype "input"))
      (node (ref "V1") (pin "16") (pinfunction "+UB_16") (pintype "power_in"))
    )
    (net (code "4") (name "9V_AC1") (class "Default")
      (node (ref "B2") (pin "AC1") (pinfunction "AC1_AC1") (pintype "passive"))
      (node (ref "B3") (pin "AC1") (pinfunction "AC1_AC1") (pintype "passive"))
      (node (ref "X12") (pin "1") (pinfunction "KL_1") (pintype "passive"))
    )
    (net (code "5") (name "9V_AC2") (class "Default")
      (node (ref "B2") (pin "AC2") (pinfunction "AC2_AC2") (pintype "passive"))
      (node (ref "B3") (pin "AC2") (pinfunction "AC2_AC2") (pintype "passive"))
      (node (ref "X12") (pin "2") (pinfunction "KL_2") (pintype "passive"))
    )
    (net (code "6") (name "A") (class "Default")
      (node (ref "J1") (pin "15") (pinfunction "15_15") (pintype "passive"))
      (node (ref "R10") (pin "1") (pinfunction "1_1") (pintype "passive"))
    )
    (net (code "7") (name "A_RX") (class "Default")
      (node (ref "IC1") (pin "14") (pinfunction "(RXD)PD0_14") (pintype "bidirectional"))
      (node (ref "JP1") (pin "8") (pinfunction "8_8") (pintype "passive"))
    )
    (net (code "8") (name "A_TX") (class "Default")
      (node (ref "IC1") (pin "15") (pinfunction "(TXD)PD1_15") (pintype "bidirectional"))
      (node (ref "JP1") (pin "6") (pinfunction "6_6") (pintype "passive"))
    )
    (net (code "9") (name "BUZZER") (class "Default")
      (node (ref "IC1") (pin "1") (pinfunction "(T0/XCK)PB0_1") (pintype "bidirectional"))
      (node (ref "SG1") (pin "+") (pinfunction "+_+") (pintype "passive"))
    )
    (net (code "10") (name "CH_PD") (class "Default")
      (node (ref "JP1") (pin "3") (pinfunction "3_3") (pintype "passive"))
      (node (ref "R4") (pin "2") (pinfunction "2_2") (pintype "passive"))
      (node (ref "SJR1") (pin "3") (pinfunction "CH_PD_3") (pintype "bidirectional"))
    )
    (net (code "11") (name "CH_PD_MEGA") (class "Default")
      (node (ref "IC1") (pin "8") (pinfunction "(SCK)PB7_8") (pintype "bidirectional"))
      (node (ref "JP1") (pin "4") (pinfunction "4_4") (pintype "passive"))
    )
    (net (code "12") (name "CON_PWM") (class "Default")
      (node (ref "IC1") (pin "19") (pinfunction "(OC1A)PD5_19") (pintype "bidirectional"))
      (node (ref "R11") (pin "2") (pinfunction "2_2") (pintype "passive"))
    )
    (net (code "13") (name "D4") (class "Default")
      (node (ref "J1") (pin "11") (pinfunction "11_11") (pintype "passive"))
      (node (ref "V1") (pin "3") (pinfunction "QD_3") (pintype "tri_state"))
    )
    (net (code "14") (name "D5") (class "Default")
      (node (ref "J1") (pin "12") (pinfunction "12_12") (pintype "passive"))
      (node (ref "V1") (pin "2") (pinfunction "QC_2") (pintype "tri_state"))
    )
    (net (code "15") (name "D6") (class "Default")
      (node (ref "J1") (pin "13") (pinfunction "13_13") (pintype "passive"))
      (node (ref "V1") (pin "1") (pinfunction "QB_1") (pintype "tri_state"))
    )
    (net (code "16") (name "D7") (class "Default")
      (node (ref "J1") (pin "14") (pinfunction "14_14") (pintype "passive"))
      (node (ref "V1") (pin "15") (pinfunction "QA_15") (pintype "tri_state"))
    )
    (net (code "17") (name "DOOR_SEN") (class "Default")
      (node (ref "IC1") (pin "7") (pinfunction "(MISO)PB6_7") (pintype "bidirectional"))
      (node (ref "X11") (pin "1") (pinfunction "KL_1") (pintype "passive"))
    )
    (net (code "18") (name "DW") (class "Default")
      (node (ref "IC1") (pin "40") (pinfunction "(ADC0)PA0_40") (pintype "bidirectional"))
      (node (ref "X14") (pin "1") (pinfunction "KL_1") (pintype "passive"))
    )
    (net (code "19") (name "EN") (class "Default")
      (node (ref "J1") (pin "6") (pinfunction "6_6") (pintype "passive"))
      (node (ref "V1") (pin "6") (pinfunction "QG_6") (pintype "tri_state"))
    )
    (net (code "20") (name "EN_HEATER_SSR") (class "Default")
      (node (ref "IC1") (pin "37") (pinfunction "(ADC3)PA3_37") (pintype "bidirectional"))
      (node (ref "X7") (pin "1") (pinfunction "KL_1") (pintype "passive"))
    )
    (net (code "21") (name "EN_PUMP") (class "Default")
      (node (ref "IC1") (pin "24") (pinfunction "(TCK)PC2_24") (pintype "bidirectional"))
      (node (ref "R23") (pin "1") (pinfunction "1_1") (pintype "passive"))
    )
    (net (code "22") (name "EN_S1_GAS") (class "Default")
      (node (ref "IC1") (pin "33") (pinfunction "(ADC7)PA7_33") (pintype "bidirectional"))
      (node (ref "R33") (pin "1") (pinfunction "1_1") (pintype "passive"))
    )
    (net (code "23") (name "EN_S2_WAT") (class "Default")
      (node (ref "IC1") (pin "26") (pinfunction "(TDO)PC4_26") (pintype "bidirectional"))
      (node (ref "R28") (pin "1") (pinfunction "1_1") (pintype "passive"))
    )
    (net (code "24") (name "EN_S3_VAP") (class "Default")
      (node (ref "IC1") (pin "28") (pinfunction "(TOSC1)PC6_28") (pintype "bidirectional"))
      (node (ref "R38") (pin "1") (pinfunction "1_1") (pintype "passive"))
    )
    (net (code "25") (name "EN_S4_DRY") (class "Default")
      (node (ref "IC1") (pin "22") (pinfunction "(SCL)PC0_22") (pintype "bidirectional"))
      (node (ref "R9") (pin "1") (pinfunction "1_1") (pintype "passive"))
    )
    (net (code "26") (name "E_0") (class "Default")
      (node (ref "SJR1") (pin "4") (pinfunction "GPIO16_4") (pintype "bidirectional"))
    )
    (net (code "27") (name "E_2") (class "Default")
      (node (ref "SJR1") (pin "7") (pinfunction "GPIO13_7") (pintype "bidirectional"))
    )
    (net (code "28") (name "E_3") (class "Default")
      (node (ref "SJR1") (pin "6") (pinfunction "GPIO12_6") (pintype "bidirectional"))
    )
    (net (code "29") (name "E_5") (class "Default")
      (node (ref "R12") (pin "2") (pinfunction "2_2") (pintype "passive"))
      (node (ref "SJR1") (pin "5") (pinfunction "GPIO14_5") (pintype "bidirectional"))
    )
    (net (code "30") (name "E_8") (class "Default")
      (node (ref "R5") (pin "1") (pinfunction "1_1") (pintype "passive"))
      (node (ref "SJR1") (pin "10") (pinfunction "GPIO15_10") (pintype "bidirectional"))
    )
    (net (code "31") (name "E_ADC") (class "Default")
      (node (ref "SJR1") (pin "2") (pinfunction "ADC_2") (pintype "bidirectional"))
    )
    (net (code "32") (name "E_RX") (class "Default")
      (node (ref "JP1") (pin "5") (pinfunction "5_5") (pintype "passive"))
      (node (ref "SJR1") (pin "15") (pinfunction "RXD_15") (pintype "bidirectional"))
    )
    (net (code "33") (name "E_TX") (class "Default")
      (node (ref "JP1") (pin "7") (pinfunction "7_7") (pintype "passive"))
      (node (ref "SJR1") (pin "16") (pinfunction "TXD_16") (pintype "bidirectional"))
    )
    (net (code "34") (name "GND") (class "Default")
      (node (ref "B2") (pin "-") (pinfunction "-_-") (pintype "passive"))
      (node (ref "C11") (pin "1") (pinfunction "1_1") (pintype "passive"))
      (node (ref "C20") (pin "2") (pinfunction "2_2") (pintype "passive"))
      (node (ref "C21") (pin "1") (pinfunction "1_1") (pintype "passive"))
      (node (ref "C22") (pin "-") (pinfunction "-_-") (pintype "passive"))
      (node (ref "C23") (pin "1") (pinfunction "1_1") (pintype "passive"))
      (node (ref "C24") (pin "1") (pinfunction "1_1") (pintype "passive"))
      (node (ref "C25") (pin "1") (pinfunction "1_1") (pintype "passive"))
      (node (ref "C26") (pin "-") (pinfunction "-_-") (pintype "passive"))
      (node (ref "C27") (pin "-") (pinfunction "-_-") (pintype "passive"))
      (node (ref "C28") (pin "1") (pinfunction "1_1") (pintype "passive"))
      (node (ref "C29") (pin "-") (pinfunction "-_-") (pintype "passive"))
      (node (ref "C3") (pin "1") (pinfunction "1_1") (pintype "passive"))
      (node (ref "C30") (pin "2") (pinfunction "2_2") (pintype "passive"))
      (node (ref "C31") (pin "2") (pinfunction "2_2") (pintype "passive"))
      (node (ref "C32") (pin "2") (pinfunction "2_2") (pintype "passive"))
      (node (ref "C33") (pin "2") (pinfunction "2_2") (pintype "passive"))
      (node (ref "C34") (pin "2") (pinfunction "2_2") (pintype "passive"))
      (node (ref "C35") (pin "2") (pinfunction "2_2") (pintype "passive"))
      (node (ref "C36") (pin "2") (pinfunction "2_2") (pintype "passive"))
      (node (ref "C4") (pin "-") (pinfunction "-_-") (pintype "passive"))
      (node (ref "C5") (pin "1") (pinfunction "1_1") (pintype "passive"))
      (node (ref "C6") (pin "2") (pinfunction "2_2") (pintype "passive"))
      (node (ref "C7") (pin "2") (pinfunction "2_2") (pintype "passive"))
      (node (ref "C8") (pin "2") (pinfunction "2_2") (pintype "passive"))
      (node (ref "D23") (pin "A") (pinfunction "A_A") (pintype "passive"))
      (node (ref "D32") (pin "A") (pinfunction "A_A") (pintype "passive"))
      (node (ref "D41") (pin "A") (pinfunction "A_A") (pintype "passive"))
      (node (ref "D50") (pin "A") (pinfunction "A_A") (pintype "passive"))
      (node (ref "D60") (pin "K") (pinfunction "C_K") (pintype "passive"))
      (node (ref "D8") (pin "A") (pinfunction "A_A") (pintype "passive"))
      (node (ref "D9") (pin "K") (pinfunction "C_K") (pintype "passive"))
      (node (ref "IC1") (pin "11") (pinfunction "GND_11") (pintype "power_in"))
      (node (ref "IC1") (pin "31") (pinfunction "GND_31") (pintype "power_in"))
      (node (ref "IC2") (pin "GND") (pinfunction "GND_GND") (pintype "input"))
      (node (ref "IC3") (pin "GND") (pinfunction "GND_GND") (pintype "input"))
      (node (ref "IC4") (pin "GND") (pinfunction "GND_GND") (pintype "input"))
      (node (ref "J1") (pin "1") (pinfunction "1_1") (pintype "passive"))
      (node (ref "J1") (pin "10") (pinfunction "10_10") (pintype "passive"))
      (node (ref "J1") (pin "16") (pinfunction "16_16") (pintype "passive"))
      (node (ref "J1") (pin "5") (pinfunction "5_5") (pintype "passive"))
      (node (ref "J1") (pin "7") (pinfunction "7_7") (pintype "passive"))
      (node (ref "J1") (pin "8") (pinfunction "8_8") (pintype "passive"))
      (node (ref "J1") (pin "9") (pinfunction "9_9") (pintype "passive"))
      (node (ref "OK1") (pin "3") (pinfunction "EMIT_3") (pintype "passive"))
      (node (ref "OK3") (pin "3") (pinfunction "EMIT_3") (pintype "passive"))
      (node (ref "OK4") (pin "3") (pinfunction "EMIT_3") (pintype "passive"))
      (node (ref "OK5") (pin "3") (pinfunction "EMIT_3") (pintype "passive"))
      (node (ref "OK6") (pin "3") (pinfunction "EMIT_3") (pintype "passive"))
      (node (ref "OK7") (pin "3") (pinfunction "EMIT_3") (pintype "passive"))
      (node (ref "R13") (pin "1") (pinfunction "1_1") (pintype "passive"))
      (node (ref "R14") (pin "1") (pinfunction "1_1") (pintype "passive"))
      (node (ref "R24") (pin "1") (pinfunction "1_1") (pintype "passive"))
      (node (ref "R29") (pin "1") (pinfunction "1_1") (pintype "passive"))
      (node (ref "R34") (pin "1") (pinfunction "1_1") (pintype "passive"))
      (node (ref "R39") (pin "1") (pinfunction "1_1") (pintype "passive"))
      (node (ref "R5") (pin "2") (pinfunction "2_2") (pintype "passive"))
      (node (ref "SJR1") (pin "9") (pinfunction "GND_9") (pintype "bidirectional"))
      (node (ref "T1") (pin "E") (pinfunction "E_E") (pintype "passive"))
      (node (ref "T3") (pin "E") (pinfunction "E_E") (pintype "passive"))
      (node (ref "T4") (pin "E") (pinfunction "E_E") (pintype "passive"))
      (node (ref "T5") (pin "E") (pinfunction "E_E") (pintype "passive"))
      (node (ref "T6") (pin "E") (pinfunction "E_E") (pintype "passive"))
      (node (ref "U$1") (pin "5") (pinfunction "GND_5") (pintype "bidirectional"))
      (node (ref "U1") (pin "1") (pinfunction "GND_1") (pintype "bidirectional"))
      (node (ref "V1") (pin "13") (pinfunction "~{G}_13") (pintype "input"))
      (node (ref "V1") (pin "8") (pinfunction "-UB_8") (pintype "power_in"))
      (node (ref "X10") (pin "2") (pinfunction "KL_2") (pintype "passive"))
      (node (ref "X11") (pin "2") (pinfunction "KL_2") (pintype "passive"))
      (node (ref "X14") (pin "2") (pinfunction "KL_2") (pintype "passive"))
      (node (ref "X7") (pin "2") (pinfunction "KL_2") (pintype "passive"))
      (node (ref "X9") (pin "2") (pinfunction "KL_2") (pintype "passive"))
    )
    (net (code "35") (name "HEATER_FED_SIG") (class "Default")
      (node (ref "IC1") (pin "36") (pinfunction "(ADC4)PA4_36") (pintype "bidirectional"))
      (node (ref "U$1") (pin "7") (pinfunction "VOUT_7") (pintype "bidirectional"))
    )
    (net (code "36") (name "HEATER_T1") (class "Default")
      (node (ref "U$1") (pin "3") (pinfunction "IP-_3") (pintype "bidirectional"))
      (node (ref "U$1") (pin "4") (pinfunction "IP-_4") (pintype "bidirectional"))
      (node (ref "X8") (pin "2") (pinfunction "KL_2") (pintype "passive"))
    )
    (net (code "37") (name "HEATER_T2") (class "Default")
      (node (ref "U$1") (pin "1") (pinfunction "IP+_1") (pintype "bidirectional"))
      (node (ref "U$1") (pin "2") (pinfunction "IP+_2") (pintype "bidirectional"))
      (node (ref "X8") (pin "1") (pinfunction "KL_1") (pintype "passive"))
    )
    (net (code "38") (name "IO0") (class "Default")
      (node (ref "R6") (pin "1") (pinfunction "1_1") (pintype "passive"))
      (node (ref "SJR1") (pin "12") (pinfunction "GPIO0_12") (pintype "bidirectional"))
    )
    (net (code "39") (name "IO2") (class "Default")
      (node (ref "SJR1") (pin "11") (pinfunction "GPIO2_11") (pintype "bidirectional"))
    )
    (net (code "40") (name "L") (class "Default")
      (node (ref "D1") (pin "C") (pinfunction "C_C") (pintype "passive"))
      (node (ref "D16") (pin "C") (pinfunction "C_C") (pintype "passive"))
      (node (ref "D21") (pin "A") (pinfunction "A_A") (pintype "passive"))
      (node (ref "D25") (pin "C") (pinfunction "C_C") (pintype "passive"))
      (node (ref "D30") (pin "A") (pinfunction "A_A") (pintype "passive"))
      (node (ref "D34") (pin "C") (pinfunction "C_C") (pintype "passive"))
      (node (ref "D39") (pin "A") (pinfunction "A_A") (pintype "passive"))
      (node (ref "D43") (pin "C") (pinfunction "C_C") (pintype "passive"))
      (node (ref "D48") (pin "A") (pinfunction "A_A") (pintype "passive"))
      (node (ref "D6") (pin "A") (pinfunction "A_A") (pintype "passive"))
      (node (ref "R1") (pin "2") (pinfunction "2_2") (pintype "passive"))
      (node (ref "R20") (pin "2") (pinfunction "2_2") (pintype "passive"))
      (node (ref "R25") (pin "2") (pinfunction "2_2") (pintype "passive"))
      (node (ref "R30") (pin "2") (pinfunction "2_2") (pintype "passive"))
      (node (ref "R35") (pin "2") (pinfunction "2_2") (pintype "passive"))
      (node (ref "X1") (pin "1") (pinfunction "KL_1") (pintype "passive"))
    )
    (net (code "41") (name "LCD_CLK") (class "Default")
      (node (ref "IC1") (pin "25") (pinfunction "(TMS)PC3_25") (pintype "bidirectional"))
      (node (ref "V1") (pin "11") (pinfunction "SRCK_11") (pintype "input"))
    )
    (net (code "42") (name "LCD_D") (class "Default")
      (node (ref "IC1") (pin "20") (pinfunction "(ICP)PD6_20") (pintype "bidirectional"))
      (node (ref "V1") (pin "14") (pinfunction "SER_14") (pintype "input"))
    )
    (net (code "43") (name "LCD_L") (class "Default")
      (node (ref "IC1") (pin "17") (pinfunction "(INT1)PD3_17") (pintype "bidirectional"))
      (node (ref "V1") (pin "12") (pinfunction "RCK_12") (pintype "input"))
    )
    (net (code "44") (name "LED_PWM") (class "Default")
      (node (ref "IC1") (pin "18") (pinfunction "(OC1B)PD4_18") (pintype "bidirectional"))
      (node (ref "R10") (pin "2") (pinfunction "2_2") (pintype "passive"))
    )
    (net (code "45") (name "N") (class "Default")
      (node (ref "X1") (pin "2") (pinfunction "KL_2") (pintype "passive"))
      (node (ref "X2") (pin "2") (pinfunction "KL_2") (pintype "passive"))
      (node (ref "X3") (pin "2") (pinfunction "KL_2") (pintype "passive"))
      (node (ref "X4") (pin "2") (pinfunction "KL_2") (pintype "passive"))
      (node (ref "X5") (pin "2") (pinfunction "KL_2") (pintype "passive"))
      (node (ref "X6") (pin "2") (pinfunction "KL_2") (pintype "passive"))
    )
    (net (code "46") (name "NRST") (class "Default")
      (node (ref "R3") (pin "2") (pinfunction "2_2") (pintype "passive"))
      (node (ref "SJR1") (pin "1") (pinfunction "REST_1") (pintype "bidirectional"))
    )
    (net (code "47") (name "Net-(B3-Pad+)") (class "Default")
      (node (ref "B3") (pin "+") (pinfunction "+_+") (pintype "passive"))
      (node (ref "R18") (pin "2") (pinfunction "2_2") (pintype "passive"))
    )
    (net (code "48") (name "Net-(C2-Pad1)") (class "Default")
      (node (ref "C2") (pin "1") (pinfunction "1_1") (pintype "passive"))
      (node (ref "D7") (pin "A") (pinfunction "A_A") (pintype "passive"))
      (node (ref "D8") (pin "C") (pinfunction "C_C") (pintype "passive"))
    )
    (net (code "49") (name "Net-(C13-Pad1)") (class "Default")
      (node (ref "C13") (pin "1") (pinfunction "1_1") (pintype "passive"))
      (node (ref "D22") (pin "A") (pinfunction "A_A") (pintype "passive"))
      (node (ref "D23") (pin "C") (pinfunction "C_C") (pintype "passive"))
    )
    (net (code "50") (name "Net-(C15-Pad1)") (class "Default")
      (node (ref "C15") (pin "1") (pinfunction "1_1") (pintype "passive"))
      (node (ref "D31") (pin "A") (pinfunction "A_A") (pintype "passive"))
      (node (ref "D32") (pin "C") (pinfunction "C_C") (pintype "passive"))
    )
    (net (code "51") (name "Net-(C17-Pad1)") (class "Default")
      (node (ref "C17") (pin "1") (pinfunction "1_1") (pintype "passive"))
      (node (ref "D40") (pin "A") (pinfunction "A_A") (pintype "passive"))
      (node (ref "D41") (pin "C") (pinfunction "C_C") (pintype "passive"))
    )
    (net (code "52") (name "Net-(C19-Pad1)") (class "Default")
      (node (ref "C19") (pin "1") (pinfunction "1_1") (pintype "passive"))
      (node (ref "D49") (pin "A") (pinfunction "A_A") (pintype "passive"))
      (node (ref "D50") (pin "C") (pinfunction "C_C") (pintype "passive"))
    )
    (net (code "53") (name "Net-(D1-PadA)") (class "Default")
      (node (ref "D1") (pin "A") (pinfunction "A_A") (pintype "passive"))
      (node (ref "D2") (pin "C") (pinfunction "C_C") (pintype "passive"))
    )
    (net (code "54") (name "Net-(D2-PadA)") (class "Default")
      (node (ref "D2") (pin "A") (pinfunction "A_A") (pintype "passive"))
      (node (ref "D3") (pin "C") (pinfunction "C_C") (pintype "passive"))
    )
    (net (code "55") (name "Net-(D4-PadA)") (class "Default")
      (node (ref "D4") (pin "A") (pinfunction "A_A") (pintype "passive"))
      (node (ref "D5") (pin "C") (pinfunction "C_C") (pintype "passive"))
    )
    (net (code "56") (name "Net-(D5-PadA)") (class "Default")
      (node (ref "D5") (pin "A") (pinfunction "A_A") (pintype "passive"))
      (node (ref "D6") (pin "C") (pinfunction "C_C") (pintype "passive"))
    )
    (net (code "57") (name "Net-(D9-PadA)") (class "Default")
      (node (ref "D9") (pin "A") (pinfunction "A_A") (pintype "passive"))
      (node (ref "R12") (pin "1") (pinfunction "1_1") (pintype "passive"))
    )
    (net (code "58") (name "Net-(D10-C)") (class "Default")
      (node (ref "D10") (pin "K") (pinfunction "C_K") (pintype "passive"))
      (node (ref "K1") (pin "4") (pinfunction "K_4") (pintype "passive"))
      (node (ref "T1") (pin "C") (pinfunction "C_C") (pintype "passive"))
    )
    (net (code "59") (name "Net-(D10-PadA)") (class "Default")
      (node (ref "D10") (pin "A") (pinfunction "A_A") (pintype "passive"))
      (node (ref "R7") (pin "1") (pinfunction "1_1") (pintype "passive"))
    )
    (net (code "60") (name "Net-(D16-PadA)") (class "Default")
      (node (ref "D16") (pin "A") (pinfunction "A_A") (pintype "passive"))
      (node (ref "D17") (pin "C") (pinfunction "C_C") (pintype "passive"))
    )
    (net (code "61") (name "Net-(D17-PadA)") (class "Default")
      (node (ref "D17") (pin "A") (pinfunction "A_A") (pintype "passive"))
      (node (ref "D18") (pin "C") (pinfunction "C_C") (pintype "passive"))
    )
    (net (code "62") (name "Net-(D19-PadA)") (class "Default")
      (node (ref "D19") (pin "A") (pinfunction "A_A") (pintype "passive"))
      (node (ref "D20") (pin "C") (pinfunction "C_C") (pintype "passive"))
    )
    (net (code "63") (name "Net-(D20-PadA)") (class "Default")
      (node (ref "D20") (pin "A") (pinfunction "A_A") (pintype "passive"))
      (node (ref "D21") (pin "C") (pinfunction "C_C") (pintype "passive"))
    )
    (net (code "64") (name "Net-(D24-C)") (class "Default")
      (node (ref "D24") (pin "K") (pinfunction "C_K") (pintype "passive"))
      (node (ref "K2") (pin "4") (pinfunction "K_4") (pintype "passive"))
      (node (ref "T3") (pin "C") (pinfunction "C_C") (pintype "passive"))
    )
    (net (code "65") (name "Net-(D24-PadA)") (class "Default")
      (node (ref "D24") (pin "A") (pinfunction "A_A") (pintype "passive"))
      (node (ref "R22") (pin "1") (pinfunction "1_1") (pintype "passive"))
    )
    (net (code "66") (name "Net-(D25-PadA)") (class "Default")
      (node (ref "D25") (pin "A") (pinfunction "A_A") (pintype "passive"))
      (node (ref "D26") (pin "C") (pinfunction "C_C") (pintype "passive"))
    )
    (net (code "67") (name "Net-(D26-PadA)") (class "Default")
      (node (ref "D26") (pin "A") (pinfunction "A_A") (pintype "passive"))
      (node (ref "D27") (pin "C") (pinfunction "C_C") (pintype "passive"))
    )
    (net (code "68") (name "Net-(D28-PadA)") (class "Default")
      (node (ref "D28") (pin "A") (pinfunction "A_A") (pintype "passive"))
      (node (ref "D29") (pin "C") (pinfunction "C_C") (pintype "passive"))
    )
    (net (code "69") (name "Net-(D29-PadA)") (class "Default")
      (node (ref "D29") (pin "A") (pinfunction "A_A") (pintype "passive"))
      (node (ref "D30") (pin "C") (pinfunction "C_C") (pintype "passive"))
    )
    (net (code "70") (name "Net-(D33-C)") (class "Default")
      (node (ref "D33") (pin "K") (pinfunction "C_K") (pintype "passive"))
      (node (ref "K3") (pin "4") (pinfunction "K_4") (pintype "passive"))
      (node (ref "T4") (pin "C") (pinfunction "C_C") (pintype "passive"))
    )
    (net (code "71") (name "Net-(D33-PadA)") (class "Default")
      (node (ref "D33") (pin "A") (pinfunction "A_A") (pintype "passive"))
      (node (ref "R27") (pin "1") (pinfunction "1_1") (pintype "passive"))
    )
    (net (code "72") (name "Net-(D34-PadA)") (class "Default")
      (node (ref "D34") (pin "A") (pinfunction "A_A") (pintype "passive"))
      (node (ref "D35") (pin "C") (pinfunction "C_C") (pintype "passive"))
    )
    (net (code "73") (name "Net-(D35-PadA)") (class "Default")
      (node (ref "D35") (pin "A") (pinfunction "A_A") (pintype "passive"))
      (node (ref "D36") (pin "C") (pinfunction "C_C") (pintype "passive"))
    )
    (net (code "74") (name "Net-(D37-PadA)") (class "Default")
      (node (ref "D37") (pin "A") (pinfunction "A_A") (pintype "passive"))
      (node (ref "D38") (pin "C") (pinfunction "C_C") (pintype "passive"))
    )
    (net (code "75") (name "Net-(D38-PadA)") (class "Default")
      (node (ref "D38") (pin "A") (pinfunction "A_A") (pintype "passive"))
      (node (ref "D39") (pin "C") (pinfunction "C_C") (pintype "passive"))
    )
    (net (code "76") (name "Net-(D42-C)") (class "Default")
      (node (ref "D42") (pin "K") (pinfunction "C_K") (pintype "passive"))
      (node (ref "K4") (pin "4") (pinfunction "K_4") (pintype "passive"))
      (node (ref "T5") (pin "C") (pinfunction "C_C") (pintype "passive"))
    )
    (net (code "77") (name "Net-(D42-PadA)") (class "Default")
      (node (ref "D42") (pin "A") (pinfunction "A_A") (pintype "passive"))
      (node (ref "R32") (pin "1") (pinfunction "1_1") (pintype "passive"))
    )
    (net (code "78") (name "Net-(D43-PadA)") (class "Default")
      (node (ref "D43") (pin "A") (pinfunction "A_A") (pintype "passive"))
      (node (ref "D44") (pin "C") (pinfunction "C_C") (pintype "passive"))
    )
    (net (code "79") (name "Net-(D44-PadA)") (class "Default")
      (node (ref "D44") (pin "A") (pinfunction "A_A") (pintype "passive"))
      (node (ref "D45") (pin "C") (pinfunction "C_C") (pintype "passive"))
    )
    (net (code "80") (name "Net-(D46-PadA)") (class "Default")
      (node (ref "D46") (pin "A") (pinfunction "A_A") (pintype "passive"))
      (node (ref "D47") (pin "C") (pinfunction "C_C") (pintype "passive"))
    )
    (net (code "81") (name "Net-(D47-PadA)") (class "Default")
      (node (ref "D47") (pin "A") (pinfunction "A_A") (pintype "passive"))
      (node (ref "D48") (pin "C") (pinfunction "C_C") (pintype "passive"))
    )
    (net (code "82") (name "Net-(D51-C)") (class "Default")
      (node (ref "D51") (pin "K") (pinfunction "C_K") (pintype "passive"))
      (node (ref "K5") (pin "4") (pinfunction "K_4") (pintype "passive"))
      (node (ref "T6") (pin "C") (pinfunction "C_C") (pintype "passive"))
    )
    (net (code "83") (name "Net-(D51-PadA)") (class "Default")
      (node (ref "D51") (pin "A") (pinfunction "A_A") (pintype "passive"))
      (node (ref "R37") (pin "1") (pinfunction "1_1") (pintype "passive"))
    )
    (net (code "84") (name "Net-(D60-PadA)") (class "Default")
      (node (ref "D60") (pin "A") (pinfunction "A_A") (pintype "passive"))
      (node (ref "R42") (pin "1") (pinfunction "1_1") (pintype "passive"))
    )
    (net (code "85") (name "Net-(IC1-XTAL1)") (class "Default")
      (node (ref "C5") (pin "2") (pinfunction "2_2") (pintype "passive"))
      (node (ref "IC1") (pin "13") (pinfunction "XTAL1_13") (pintype "bidirectional"))
      (node (ref "Q1") (pin "1") (pinfunction "1_1") (pintype "passive"))
    )
    (net (code "86") (name "Net-(IC1-XTAL2)") (class "Default")
      (node (ref "C3") (pin "2") (pinfunction "2_2") (pintype "passive"))
      (node (ref "IC1") (pin "12") (pinfunction "XTAL2_12") (pintype "bidirectional"))
      (node (ref "Q1") (pin "2") (pinfunction "2_2") (pintype "passive"))
    )
    (net (code "87") (name "Net-(K1-DS2)") (class "Default")
      (node (ref "D3") (pin "A") (pinfunction "A_A") (pintype "passive"))
      (node (ref "D4") (pin "C") (pinfunction "C_C") (pintype "passive"))
      (node (ref "K1") (pin "2") (pinfunction "DS2_2") (pintype "passive"))
      (node (ref "OK1") (pin "2") (pinfunction "C_2") (pintype "passive"))
    )
    (net (code "88") (name "Net-(K2-DS2)") (class "Default")
      (node (ref "D18") (pin "A") (pinfunction "A_A") (pintype "passive"))
      (node (ref "D19") (pin "C") (pinfunction "C_C") (pintype "passive"))
      (node (ref "K2") (pin "2") (pinfunction "DS2_2") (pintype "passive"))
      (node (ref "OK3") (pin "2") (pinfunction "C_2") (pintype "passive"))
    )
    (net (code "89") (name "Net-(K3-DS2)") (class "Default")
      (node (ref "D27") (pin "A") (pinfunction "A_A") (pintype "passive"))
      (node (ref "D28") (pin "C") (pinfunction "C_C") (pintype "passive"))
      (node (ref "K3") (pin "2") (pinfunction "DS2_2") (pintype "passive"))
      (node (ref "OK4") (pin "2") (pinfunction "C_2") (pintype "passive"))
    )
    (net (code "90") (name "Net-(K4-DS2)") (class "Default")
      (node (ref "D36") (pin "A") (pinfunction "A_A") (pintype "passive"))
      (node (ref "D37") (pin "C") (pinfunction "C_C") (pintype "passive"))
      (node (ref "K4") (pin "2") (pinfunction "DS2_2") (pintype "passive"))
      (node (ref "OK5") (pin "2") (pinfunction "C_2") (pintype "passive"))
    )
    (net (code "91") (name "Net-(K5-DS2)") (class "Default")
      (node (ref "D45") (pin "A") (pinfunction "A_A") (pintype "passive"))
      (node (ref "D46") (pin "C") (pinfunction "C_C") (pintype "passive"))
      (node (ref "K5") (pin "2") (pinfunction "DS2_2") (pintype "passive"))
      (node (ref "OK6") (pin "2") (pinfunction "C_2") (pintype "passive"))
    )
    (net (code "92") (name "Net-(OK1-A)") (class "Default")
      (node (ref "OK1") (pin "1") (pinfunction "A_1") (pintype "passive"))
      (node (ref "R1") (pin "1") (pinfunction "1_1") (pintype "passive"))
    )
    (net (code "93") (name "Net-(OK1-COL)") (class "Default")
      (node (ref "C2") (pin "2") (pinfunction "2_2") (pintype "passive"))
      (node (ref "OK1") (pin "4") (pinfunction "COL_4") (pintype "passive"))
      (node (ref "R2") (pin "1") (pinfunction "1_1") (pintype "passive"))
    )
    (net (code "94") (name "Net-(OK3-A)") (class "Default")
      (node (ref "OK3") (pin "1") (pinfunction "A_1") (pintype "passive"))
      (node (ref "R20") (pin "1") (pinfunction "1_1") (pintype "passive"))
    )
    (net (code "95") (name "Net-(OK3-COL)") (class "Default")
      (node (ref "C13") (pin "2") (pinfunction "2_2") (pintype "passive"))
      (node (ref "OK3") (pin "4") (pinfunction "COL_4") (pintype "passive"))
      (node (ref "R21") (pin "1") (pinfunction "1_1") (pintype "passive"))
    )
    (net (code "96") (name "Net-(OK4-A)") (class "Default")
      (node (ref "OK4") (pin "1") (pinfunction "A_1") (pintype "passive"))
      (node (ref "R25") (pin "1") (pinfunction "1_1") (pintype "passive"))
    )
    (net (code "97") (name "Net-(OK4-COL)") (class "Default")
      (node (ref "C15") (pin "2") (pinfunction "2_2") (pintype "passive"))
      (node (ref "OK4") (pin "4") (pinfunction "COL_4") (pintype "passive"))
      (node (ref "R26") (pin "1") (pinfunction "1_1") (pintype "passive"))
    )
    (net (code "98") (name "Net-(OK5-A)") (class "Default")
      (node (ref "OK5") (pin "1") (pinfunction "A_1") (pintype "passive"))
      (node (ref "R30") (pin "1") (pinfunction "1_1") (pintype "passive"))
    )
    (net (code "99") (name "Net-(OK5-COL)") (class "Default")
      (node (ref "C17") (pin "2") (pinfunction "2_2") (pintype "passive"))
      (node (ref "OK5") (pin "4") (pinfunction "COL_4") (pintype "passive"))
      (node (ref "R31") (pin "1") (pinfunction "1_1") (pintype "passive"))
    )
    (net (code "100") (name "Net-(OK6-A)") (class "Default")
      (node (ref "OK6") (pin "1") (pinfunction "A_1") (pintype "passive"))
      (node (ref "R35") (pin "1") (pinfunction "1_1") (pintype "passive"))
    )
    (net (code "101") (name "Net-(OK6-COL)") (class "Default")
      (node (ref "C19") (pin "2") (pinfunction "2_2") (pintype "passive"))
      (node (ref "OK6") (pin "4") (pinfunction "COL_4") (pintype "passive"))
      (node (ref "R36") (pin "1") (pinfunction "1_1") (pintype "passive"))
    )
    (net (code "102") (name "Net-(OK7-A)") (class "Default")
      (node (ref "OK7") (pin "1") (pinfunction "A_1") (pintype "passive"))
      (node (ref "R18") (pin "1") (pinfunction "1_1") (pintype "passive"))
    )
    (net (code "103") (name "Net-(OK7-C)") (class "Default")
      (node (ref "B3") (pin "-") (pinfunction "-_-") (pintype "passive"))
      (node (ref "OK7") (pin "2") (pinfunction "C_2") (pintype "passive"))
    )
    (net (code "104") (name "Net-(R9-Pad2)") (class "Default")
      (node (ref "R9") (pin "2") (pinfunction "2_2") (pintype "passive"))
      (node (ref "T1") (pin "B") (pinfunction "B_B") (pintype "passive"))
    )
    (net (code "105") (name "Net-(R14-Pad2)") (class "Default")
      (node (ref "R14") (pin "2") (pinfunction "2_2") (pintype "passive"))
      (node (ref "SG1") (pin "-") (pinfunction "-_-") (pintype "passive"))
    )
    (net (code "106") (name "Net-(R23-Pad2)") (class "Default")
      (node (ref "R23") (pin "2") (pinfunction "2_2") (pintype "passive"))
      (node (ref "T3") (pin "B") (pinfunction "B_B") (pintype "passive"))
    )
    (net (code "107") (name "Net-(R28-Pad2)") (class "Default")
      (node (ref "R28") (pin "2") (pinfunction "2_2") (pintype "passive"))
      (node (ref "T4") (pin "B") (pinfunction "B_B") (pintype "passive"))
    )
    (net (code "108") (name "Net-(R33-Pad2)") (class "Default")
      (node (ref "R33") (pin "2") (pinfunction "2_2") (pintype "passive"))
      (node (ref "T5") (pin "B") (pinfunction "B_B") (pintype "passive"))
    )
    (net (code "109") (name "Net-(R38-Pad2)") (class "Default")
      (node (ref "R38") (pin "2") (pinfunction "2_2") (pintype "passive"))
      (node (ref "T6") (pin "B") (pinfunction "B_B") (pintype "passive"))
    )
    (net (code "110") (name "Net-(U$1-FILT)") (class "Default")
      (node (ref "C31") (pin "1") (pinfunction "1_1") (pintype "passive"))
      (node (ref "U$1") (pin "6") (pinfunction "FILT_6") (pintype "bidirectional"))
    )
    (net (code "111") (name "OK") (class "Default")
      (node (ref "IC1") (pin "39") (pinfunction "(ADC1)PA1_39") (pintype "bidirectional"))
      (node (ref "X13") (pin "2") (pinfunction "KL_2") (pintype "passive"))
    )
    (net (code "112") (name "OUT_PUMP") (class "Default")
      (node (ref "K5") (pin "1") (pinfunction "DS1_1") (pintype "passive"))
      (node (ref "X6") (pin "1") (pinfunction "KL_1") (pintype "passive"))
    )
    (net (code "113") (name "OUT_S1_GAS") (class "Default")
      (node (ref "K4") (pin "1") (pinfunction "DS1_1") (pintype "passive"))
      (node (ref "X2") (pin "1") (pinfunction "KL_1") (pintype "passive"))
    )
    (net (code "114") (name "OUT_S2_WAT") (class "Default")
      (node (ref "K3") (pin "1") (pinfunction "DS1_1") (pintype "passive"))
      (node (ref "X3") (pin "1") (pinfunction "KL_1") (pintype "passive"))
    )
    (net (code "115") (name "OUT_S3_VAP") (class "Default")
      (node (ref "K2") (pin "1") (pinfunction "DS1_1") (pintype "passive"))
      (node (ref "X4") (pin "1") (pinfunction "KL_1") (pintype "passive"))
    )
    (net (code "116") (name "OUT_S4_DRY") (class "Default")
      (node (ref "K1") (pin "1") (pinfunction "DS1_1") (pintype "passive"))
      (node (ref "X5") (pin "1") (pinfunction "KL_1") (pintype "passive"))
    )
    (net (code "117") (name "PRES_SEN") (class "Default")
      (node (ref "IC1") (pin "6") (pinfunction "(MOSI)PB5_6") (pintype "bidirectional"))
      (node (ref "X10") (pin "1") (pinfunction "KL_1") (pintype "passive"))
    )
    (net (code "118") (name "PUMP_FED_SIG") (class "Default")
      (node (ref "C33") (pin "1") (pinfunction "1_1") (pintype "passive"))
      (node (ref "D22") (pin "C") (pinfunction "C_C") (pintype "passive"))
      (node (ref "IC1") (pin "23") (pinfunction "(SDA)PC1_23") (pintype "bidirectional"))
      (node (ref "R24") (pin "2") (pinfunction "2_2") (pintype "passive"))
    )
    (net (code "119") (name "REST") (class "Default")
      (node (ref "IC1") (pin "9") (pinfunction "RESET_9") (pintype "input"))
      (node (ref "JP1") (pin "2") (pinfunction "2_2") (pintype "passive"))
      (node (ref "R8") (pin "1") (pinfunction "1_1") (pintype "passive"))
    )
    (net (code "120") (name "REST_OUT") (class "Default")
      (node (ref "JP1") (pin "1") (pinfunction "1_1") (pintype "passive"))
      (node (ref "SJR1") (pin "13") (pinfunction "GPIO4_13") (pintype "bidirectional"))
    )
    (net (code "121") (name "RS") (class "Default")
      (node (ref "J1") (pin "4") (pinfunction "4_4") (pintype "passive"))
      (node (ref "V1") (pin "7") (pinfunction "QH_7") (pintype "tri_state"))
    )
    (net (code "122") (name "S1_GAS_FED_SIG") (class "Default")
      (node (ref "C35") (pin "1") (pinfunction "1_1") (pintype "passive"))
      (node (ref "D40") (pin "C") (pinfunction "C_C") (pintype "passive"))
      (node (ref "IC1") (pin "35") (pinfunction "(ADC5)PA5_35") (pintype "bidirectional"))
      (node (ref "R34") (pin "2") (pinfunction "2_2") (pintype "passive"))
    )
    (net (code "123") (name "S2_WAT_FED_SIG") (class "Default")
      (node (ref "C34") (pin "1") (pinfunction "1_1") (pintype "passive"))
      (node (ref "D31") (pin "C") (pinfunction "C_C") (pintype "passive"))
      (node (ref "IC1") (pin "27") (pinfunction "(TDI)PC5_27") (pintype "bidirectional"))
      (node (ref "R29") (pin "2") (pinfunction "2_2") (pintype "passive"))
    )
    (net (code "124") (name "S3_VAP_FED_SIG") (class "Default")
      (node (ref "C36") (pin "1") (pinfunction "1_1") (pintype "passive"))
      (node (ref "D49") (pin "C") (pinfunction "C_C") (pintype "passive"))
      (node (ref "IC1") (pin "29") (pinfunction "(TOSC2)PC7_29") (pintype "bidirectional"))
      (node (ref "R39") (pin "2") (pinfunction "2_2") (pintype "passive"))
    )
    (net (code "125") (name "S4_DRY_FED_SIG") (class "Default")
      (node (ref "C32") (pin "1") (pinfunction "1_1") (pintype "passive"))
      (node (ref "D7") (pin "C") (pinfunction "C_C") (pintype "passive"))
      (node (ref "IC1") (pin "21") (pinfunction "(OC2)PD7_21") (pintype "bidirectional"))
      (node (ref "R13") (pin "2") (pinfunction "2_2") (pintype "passive"))
    )
    (net (code "126") (name "SCL3") (class "Default")
      (node (ref "SJR1") (pin "14") (pinfunction "GPIO5_14") (pintype "bidirectional"))
    )
    (net (code "127") (name "TCK+") (class "Default")
      (node (ref "U1") (pin "3") (pinfunction "T+_3") (pintype "bidirectional"))
      (node (ref "X15") (pin "2") (pinfunction "KL_2") (pintype "passive"))
    )
    (net (code "128") (name "TCK-") (class "Default")
      (node (ref "U1") (pin "2") (pinfunction "T-_2") (pintype "bidirectional"))
      (node (ref "X15") (pin "1") (pinfunction "KL_1") (pintype "passive"))
    )
    (net (code "129") (name "T_CLK") (class "Default")
      (node (ref "IC1") (pin "3") (pinfunction "(AIN0/INT2)PB2_3") (pintype "bidirectional"))
      (node (ref "U1") (pin "6") (pinfunction "~{CS}_6") (pintype "bidirectional"))
    )
    (net (code "130") (name "T_CS") (class "Default")
      (node (ref "IC1") (pin "2") (pinfunction "(T1)PB1_2") (pintype "bidirectional"))
      (node (ref "U1") (pin "5") (pinfunction "SCK_5") (pintype "bidirectional"))
    )
    (net (code "131") (name "T_DO") (class "Default")
      (node (ref "IC1") (pin "4") (pinfunction "(AIN1/OC0)PB3_4") (pintype "bidirectional"))
      (node (ref "U1") (pin "7") (pinfunction "(MI)SO_7") (pintype "bidirectional"))
    )
    (net (code "132") (name "UP") (class "Default")
      (node (ref "IC1") (pin "38") (pinfunction "(ADC2)PA2_38") (pintype "bidirectional"))
      (node (ref "X13") (pin "1") (pinfunction "KL_1") (pintype "passive"))
    )
    (net (code "133") (name "VEE") (class "Default")
      (node (ref "C11") (pin "2") (pinfunction "2_2") (pintype "passive"))
      (node (ref "C4") (pin "+") (pinfunction "+_+") (pintype "passive"))
      (node (ref "J1") (pin "3") (pinfunction "3_3") (pintype "passive"))
      (node (ref "R11") (pin "1") (pinfunction "1_1") (pintype "passive"))
    )
    (net (code "134") (name "VIN") (class "Default")
      (node (ref "B2") (pin "+") (pinfunction "+_+") (pintype "passive"))
      (node (ref "C22") (pin "+") (pinfunction "+_+") (pintype "passive"))
      (node (ref "C23") (pin "2") (pinfunction "2_2") (pintype "passive"))
      (node (ref "IC2") (pin "IN") (pinfunction "IN_IN") (pintype "input"))
      (node (ref "IC4") (pin "IN") (pinfunction "IN_IN") (pintype "input"))
      (node (ref "R42") (pin "2") (pinfunction "2_2") (pintype "passive"))
    )
    (net (code "135") (name "WATER_SEN") (class "Default")
      (node (ref "IC1") (pin "5") (pinfunction "(SS)PB4_5") (pintype "bidirectional"))
      (node (ref "X9") (pin "1") (pinfunction "KL_1") (pintype "passive"))
    )
    (net (code "136") (name "ZERO_CROSS") (class "Default")
      (node (ref "IC1") (pin "16") (pinfunction "(INT0)PD2_16") (pintype "bidirectional"))
      (node (ref "OK7") (pin "4") (pinfunction "COL_4") (pintype "passive"))
      (node (ref "R19") (pin "2") (pinfunction "2_2") (pintype "passive"))
    )
    (net (code "137") (name "unconnected-(IC1-(ADC6)PA6-Pad34)") (class "Default")
      (node (ref "IC1") (pin "34") (pinfunction "(ADC6)PA6_34") (pintype "bidirectional"))
    )
    (net (code "138") (name "unconnected-(IC1-AREF-Pad32)") (class "Default")
      (node (ref "IC1") (pin "32") (pinfunction "AREF_32") (pintype "passive"))
    )
    (net (code "139") (name "unconnected-(SJR1-CS0-Pad17)") (class "Default")
      (node (ref "SJR1") (pin "17") (pinfunction "CS0_17") (pintype "bidirectional"))
    )
    (net (code "140") (name "unconnected-(SJR1-GPIO9-Pad19)") (class "Default")
      (node (ref "SJR1") (pin "19") (pinfunction "GPIO9_19") (pintype "bidirectional"))
    )
    (net (code "141") (name "unconnected-(SJR1-GPIO10-Pad20)") (class "Default")
      (node (ref "SJR1") (pin "20") (pinfunction "GPIO10_20") (pintype "bidirectional"))
    )
    (net (code "142") (name "unconnected-(SJR1-MISO-Pad18)") (class "Default")
      (node (ref "SJR1") (pin "18") (pinfunction "MISO_18") (pintype "bidirectional"))
    )
    (net (code "143") (name "unconnected-(SJR1-MOSI-Pad21)") (class "Default")
      (node (ref "SJR1") (pin "21") (pinfunction "MOSI_21") (pintype "bidirectional"))
    )
    (net (code "144") (name "unconnected-(SJR1-SCLK-Pad22)") (class "Default")
      (node (ref "SJR1") (pin "22") (pinfunction "SCLK_22") (pintype "bidirectional"))
    )
    (net (code "145") (name "unconnected-(V1C-QE-Pad4)") (class "Default")
      (node (ref "V1") (pin "4") (pinfunction "QE_4") (pintype "tri_state"))
    )
    (net (code "146") (name "unconnected-(V1C-QF-Pad5)") (class "Default")
      (node (ref "V1") (pin "5") (pinfunction "QF_5") (pintype "tri_state"))
    )
    (net (code "147") (name "unconnected-(V1C-QH*-Pad9)") (class "Default")
      (node (ref "V1") (pin "9") (pinfunction "QH*_9") (pintype "output"))
    )
  )
)
